# STB_UID.net
KiCad netlist of a schematic drawn in Altium Designer
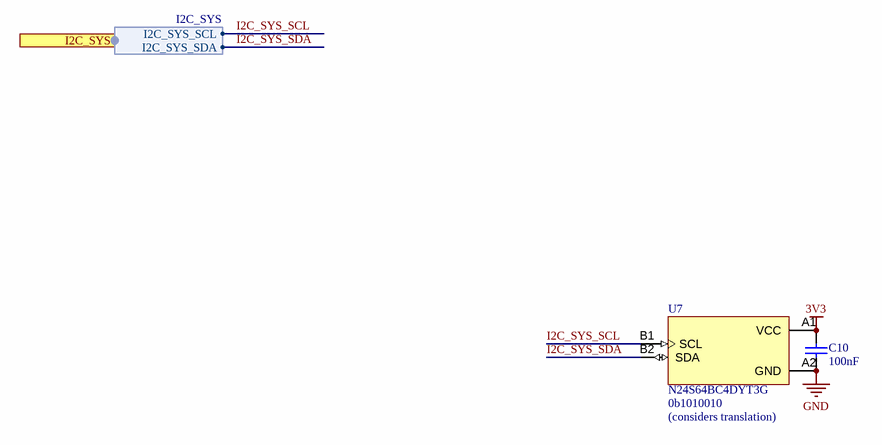
[diagram p0: STB_UID.SchDoc]

(export (version "E")
  (design (tool "Eeschema 10.0.6"))
  (components
    (comp (ref "C10")
      (value "100nF")
      (footprint "CAPC1050X55X23LL05T13")
      (description "Chip Capacitor, 100 nF, +/- 10%, 16 V, -55 to 125 degC, 0402 (1005 Metric), RoHS, Tape and Reel")
      (fields
        (field (name "MANUFACTURER") "Samsung Electro-Mechanics")
        (field (name "MANUFACTURER PART NUMBER") "CL05B104KO5NNNC")
      )
      (libsource (lib "Altium Content Vault") (part "CAP-NP-2"))
    )
    (comp (ref "U7")
      (value "N24S64BC4DYT3G")
      (footprint "4-WLCSP (0.77x0.77)")
      (description "Memory IC 64Kb (8K x 8) I²C 1 MHz 400 ns 4-WLCSP (0.77x0.77)")
      (fields (field (name "MFR") "onsemi") (field (name "MANUFACTURER") "ON Semiconductor"))
      (libsource (lib "ETHZ Vault") (part "N24S64BC4DYT3G"))
    )
  )
  (nets
    (net (code "2") (name "/I2C_SYS_SCL") (class "Default")
      (node (ref "U7") (pin "B1") (pinfunction "SCL_B1") (pintype "input"))
    )
    (net (code "3") (name "/I2C_SYS_SDA") (class "Default")
      (node (ref "U7") (pin "B2") (pinfunction "SDA_B2") (pintype "bidirectional"))
    )
    (net (code "5") (name "3V3") (class "Default")
      (node (ref "C10") (pin "2") (pinfunction "2_2") (pintype "passive"))
      (node (ref "U7") (pin "A1") (pinfunction "VCC_A1") (pintype "power_in"))
    )
    (net (code "6") (name "GND") (class "Default")
      (node (ref "C10") (pin "1") (pinfunction "1_1") (pintype "passive"))
      (node (ref "U7") (pin "A2") (pinfunction "GND_A2") (pintype "power_in"))
    )
  )
)
